# Motherboard.net
KiCad netlist of a schematic drawn in Altium Designer
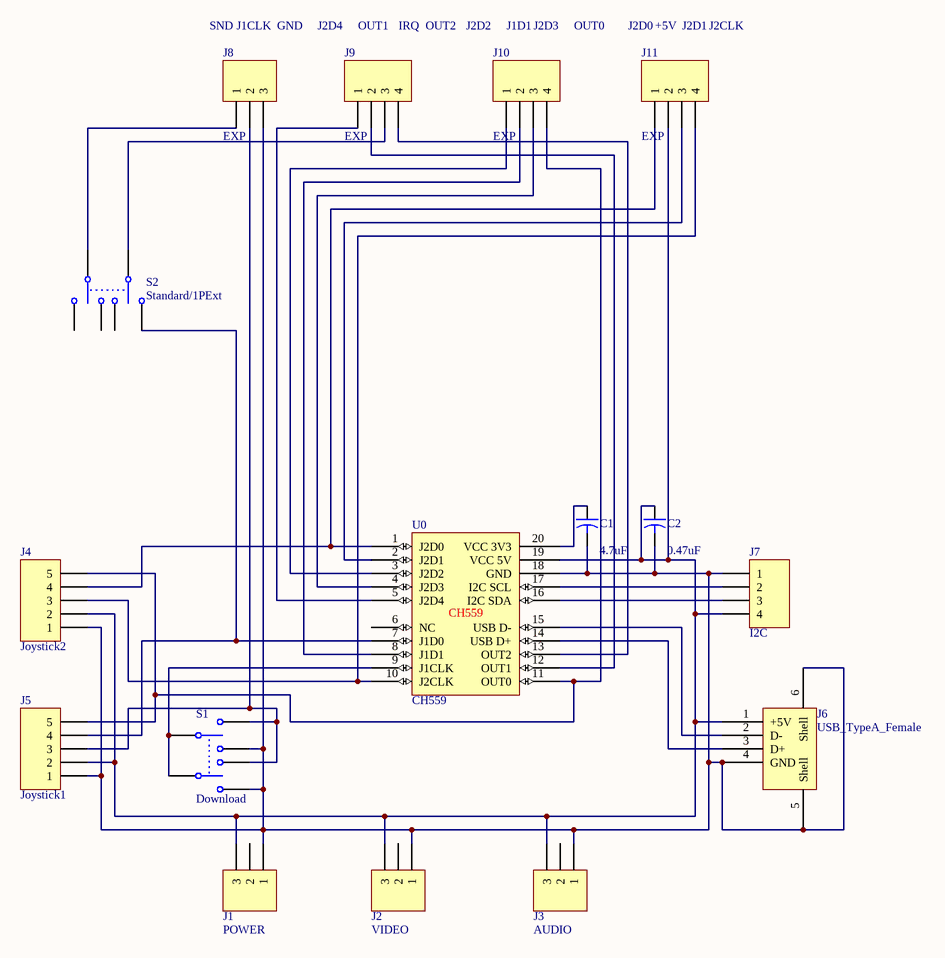
[diagram p0: Motherboard.SchDoc]

(export (version "E")
  (design (tool "Eeschema 10.0.6"))
  (components
    (comp (ref "C1")
      (value "4.7uF")
      (footprint "CAPR5-4X5")
      (description "Capacitor")
      (fields (field (name "Comment") "Cap2") (field (name "PUBLISHER") "Altium Limited"))
      (libsource (lib "Miscellaneous Devices") (part "Cap2"))
    )
    (comp (ref "C2")
      (value "0.47uF")
      (footprint "CAPR5-4X5")
      (description "Capacitor")
      (fields (field (name "Comment") "Cap2") (field (name "PUBLISHER") "Altium Limited"))
      (libsource (lib "Miscellaneous Devices") (part "Cap2"))
    )
    (comp (ref "J1")
      (value "POWER")
      (footprint "HDR1X3H")
      (description "Header, 3-Pin, Right Angle")
      (fields (field (name "PUBLISHER") "Altium Limited"))
      (libsource (lib "Miscellaneous Connectors") (part "Header 3H"))
    )
    (comp (ref "J2")
      (value "VIDEO")
      (footprint "HDR1X3H")
      (description "Header, 3-Pin, Right Angle")
      (fields (field (name "PUBLISHER") "Altium Limited"))
      (libsource (lib "Miscellaneous Connectors") (part "Header 3H"))
    )
    (comp (ref "J3")
      (value "AUDIO")
      (footprint "HDR1X3H")
      (description "Header, 3-Pin, Right Angle")
      (fields (field (name "PUBLISHER") "Altium Limited"))
      (libsource (lib "Miscellaneous Connectors") (part "Header 3H"))
    )
    (comp (ref "J4")
      (value "Joystick2")
      (footprint "HDR1X5H")
      (description "Header, 5-Pin, Right Angle")
      (fields (field (name "PUBLISHER") "Altium Limited"))
      (libsource (lib "Miscellaneous Connectors") (part "Header 5H"))
    )
    (comp (ref "J5")
      (value "Joystick1")
      (footprint "HDR1X5H")
      (description "Header, 5-Pin, Right Angle")
      (fields (field (name "PUBLISHER") "Altium Limited"))
      (libsource (lib "Miscellaneous Connectors") (part "Header 5H"))
    )
    (comp (ref "J6")
      (value "USB_TypeA_Female")
      (footprint "USB_TypeA_Female")
      (libsource (lib "USB_TypeA_Female") (part "USB_TypeA_Female"))
    )
    (comp (ref "J7")
      (value "I2C")
      (footprint "HDR1X4H")
      (description "Header, 4-Pin, Right Angle")
      (fields (field (name "PUBLISHER") "Altium Limited"))
      (libsource (lib "") (part "Header 4H_1"))
    )
    (comp (ref "J8")
      (value "EXP")
      (footprint "HDR1X3H")
      (description "Header, 3-Pin, Right Angle")
      (fields (field (name "PUBLISHER") "Altium Limited"))
      (libsource (lib "") (part "Header 3H_1"))
    )
    (comp (ref "J9")
      (value "EXP")
      (footprint "HDR1X4H")
      (description "Header, 4-Pin, Right Angle")
      (fields (field (name "PUBLISHER") "Altium Limited"))
      (libsource (lib "Miscellaneous Connectors") (part "Header 4H"))
    )
    (comp (ref "J10")
      (value "EXP")
      (footprint "HDR1X4H")
      (description "Header, 4-Pin, Right Angle")
      (fields (field (name "PUBLISHER") "Altium Limited"))
      (libsource (lib "Miscellaneous Connectors") (part "Header 4H"))
    )
    (comp (ref "J11")
      (value "EXP")
      (footprint "HDR1X4H")
      (description "Header, 4-Pin, Right Angle")
      (fields (field (name "PUBLISHER") "Altium Limited"))
      (libsource (lib "Miscellaneous Connectors") (part "Header 4H"))
    )
    (comp (ref "S1")
      (value "Download")
      (footprint "DPDT-6")
      (description "Double-Pole, Double-Throw Switch")
      (fields (field (name "PUBLISHER") "Altium Limited"))
      (libsource (lib "Miscellaneous Devices") (part "SW-DPDT"))
    )
    (comp (ref "S2")
      (value "Standard/1PExt")
      (footprint "DPDT-6")
      (description "Double-Pole, Double-Throw Switch")
      (fields (field (name "PUBLISHER") "Altium Limited"))
      (libsource (lib "Miscellaneous Devices") (part "SW-DPDT"))
    )
    (comp (ref "U0") (value "CH559") (footprint "SSOP20") (libsource (lib "CH559") (part "CH559")))
  )
  (nets
    (net (code "1") (name "Net-(J5-Pad3)") (class "Default")
      (node (ref "J5") (pin "3") (pinfunction "3_3") (pintype "passive"))
      (node (ref "J8") (pin "2") (pinfunction "2_2") (pintype "passive"))
      (node (ref "S1") (pin "2") (pinfunction "2_2") (pintype "passive"))
      (node (ref "S1") (pin "5") (pinfunction "5_5") (pintype "passive"))
    )
    (net (code "2") (name "Net-(J6-+5V)") (class "Default")
      (node (ref "C2") (pin "1") (pinfunction "1_1") (pintype "passive"))
      (node (ref "J1") (pin "3") (pinfunction "3_3") (pintype "passive"))
      (node (ref "J11") (pin "2") (pinfunction "2_2") (pintype "passive"))
      (node (ref "J2") (pin "3") (pinfunction "3_3") (pintype "passive"))
      (node (ref "J3") (pin "3") (pinfunction "3_3") (pintype "passive"))
      (node (ref "J4") (pin "2") (pinfunction "2_2") (pintype "passive"))
      (node (ref "J5") (pin "2") (pinfunction "2_2") (pintype "passive"))
      (node (ref "J6") (pin "1") (pinfunction "+5V_1") (pintype "passive"))
      (node (ref "J7") (pin "4") (pinfunction "4_4") (pintype "passive"))
      (node (ref "U0") (pin "19") (pinfunction "VCC_5V_19") (pintype "power_in"))
    )
    (net (code "3") (name "Net-(J6-D+)") (class "Default")
      (node (ref "J6") (pin "3") (pinfunction "D+_3") (pintype "passive"))
      (node (ref "U0") (pin "14") (pinfunction "USB_D+_14") (pintype "bidirectional"))
    )
    (net (code "4") (name "Net-(J6-D-)") (class "Default")
      (node (ref "J6") (pin "2") (pinfunction "D-_2") (pintype "passive"))
      (node (ref "U0") (pin "15") (pinfunction "USB_D-_15") (pintype "bidirectional"))
    )
    (net (code "5") (name "Net-(J6-GND)") (class "Default")
      (node (ref "C1") (pin "2") (pinfunction "2_2") (pintype "passive"))
      (node (ref "C2") (pin "2") (pinfunction "2_2") (pintype "passive"))
      (node (ref "J1") (pin "1") (pinfunction "1_1") (pintype "passive"))
      (node (ref "J2") (pin "1") (pinfunction "1_1") (pintype "passive"))
      (node (ref "J3") (pin "1") (pinfunction "1_1") (pintype "passive"))
      (node (ref "J4") (pin "1") (pinfunction "1_1") (pintype "passive"))
      (node (ref "J5") (pin "1") (pinfunction "1_1") (pintype "passive"))
      (node (ref "J6") (pin "4") (pinfunction "GND_4") (pintype "passive"))
      (node (ref "J6") (pin "5") (pinfunction "Shell_5") (pintype "passive"))
      (node (ref "J6") (pin "6") (pinfunction "Shell_6") (pintype "passive"))
      (node (ref "J7") (pin "1") (pinfunction "1_1") (pintype "passive"))
      (node (ref "J8") (pin "3") (pinfunction "3_3") (pintype "passive"))
      (node (ref "S1") (pin "3") (pinfunction "3_3") (pintype "passive"))
      (node (ref "S1") (pin "6") (pinfunction "6_6") (pintype "passive"))
      (node (ref "U0") (pin "18") (pinfunction "GND_18") (pintype "power_in"))
    )
    (net (code "6") (name "Net-(J8-Pad1)") (class "Default")
      (node (ref "J8") (pin "1") (pinfunction "1_1") (pintype "passive"))
      (node (ref "S2") (pin "4") (pinfunction "4_4") (pintype "passive"))
    )
    (net (code "7") (name "Net-(J9-Pad3)") (class "Default")
      (node (ref "J9") (pin "3") (pinfunction "3_3") (pintype "passive"))
      (node (ref "S2") (pin "1") (pinfunction "1_1") (pintype "passive"))
    )
    (net (code "8") (name "Net-(U0-I2C_SCL)") (class "Default")
      (node (ref "J7") (pin "2") (pinfunction "2_2") (pintype "passive"))
      (node (ref "U0") (pin "17") (pinfunction "I2C_SCL_17") (pintype "bidirectional"))
    )
    (net (code "9") (name "Net-(U0-I2C_SDA)") (class "Default")
      (node (ref "J7") (pin "3") (pinfunction "3_3") (pintype "passive"))
      (node (ref "U0") (pin "16") (pinfunction "I2C_SDA_16") (pintype "bidirectional"))
    )
    (net (code "10") (name "Net-(U0-J1CLK)") (class "Default")
      (node (ref "S1") (pin "1") (pinfunction "1_1") (pintype "passive"))
      (node (ref "S1") (pin "4") (pinfunction "4_4") (pintype "passive"))
      (node (ref "U0") (pin "9") (pinfunction "J1CLK_9") (pintype "bidirectional"))
    )
    (net (code "11") (name "Net-(U0-J1D0)") (class "Default")
      (node (ref "J5") (pin "4") (pinfunction "4_4") (pintype "passive"))
      (node (ref "S2") (pin "2") (pinfunction "2_2") (pintype "passive"))
      (node (ref "U0") (pin "7") (pinfunction "J1D0_7") (pintype "bidirectional"))
    )
    (net (code "12") (name "Net-(U0-J1D1)") (class "Default")
      (node (ref "J10") (pin "2") (pinfunction "2_2") (pintype "passive"))
      (node (ref "U0") (pin "8") (pinfunction "J1D1_8") (pintype "bidirectional"))
    )
    (net (code "13") (name "Net-(U0-J2CLK)") (class "Default")
      (node (ref "J11") (pin "4") (pinfunction "4_4") (pintype "passive"))
      (node (ref "J4") (pin "3") (pinfunction "3_3") (pintype "passive"))
      (node (ref "U0") (pin "10") (pinfunction "J2CLK_10") (pintype "bidirectional"))
    )
    (net (code "14") (name "Net-(U0-J2D0)") (class "Default")
      (node (ref "J11") (pin "1") (pinfunction "1_1") (pintype "passive"))
      (node (ref "J4") (pin "4") (pinfunction "4_4") (pintype "passive"))
      (node (ref "U0") (pin "1") (pinfunction "J2D0_1") (pintype "bidirectional"))
    )
    (net (code "15") (name "Net-(U0-J2D1)") (class "Default")
      (node (ref "J11") (pin "3") (pinfunction "3_3") (pintype "passive"))
      (node (ref "U0") (pin "2") (pinfunction "J2D1_2") (pintype "bidirectional"))
    )
    (net (code "16") (name "Net-(U0-J2D2)") (class "Default")
      (node (ref "J10") (pin "1") (pinfunction "1_1") (pintype "passive"))
      (node (ref "U0") (pin "3") (pinfunction "J2D2_3") (pintype "bidirectional"))
    )
    (net (code "17") (name "Net-(U0-J2D3)") (class "Default")
      (node (ref "J10") (pin "3") (pinfunction "3_3") (pintype "passive"))
      (node (ref "U0") (pin "4") (pinfunction "J2D3_4") (pintype "bidirectional"))
    )
    (net (code "18") (name "Net-(U0-J2D4)") (class "Default")
      (node (ref "J9") (pin "1") (pinfunction "1_1") (pintype "passive"))
      (node (ref "U0") (pin "5") (pinfunction "J2D4_5") (pintype "bidirectional"))
    )
    (net (code "19") (name "Net-(U0-OUT0)") (class "Default")
      (node (ref "J10") (pin "4") (pinfunction "4_4") (pintype "passive"))
      (node (ref "J4") (pin "5") (pinfunction "5_5") (pintype "passive"))
      (node (ref "J5") (pin "5") (pinfunction "5_5") (pintype "passive"))
      (node (ref "U0") (pin "11") (pinfunction "OUT0_11") (pintype "bidirectional"))
    )
    (net (code "20") (name "Net-(U0-OUT1)") (class "Default")
      (node (ref "J9") (pin "2") (pinfunction "2_2") (pintype "passive"))
      (node (ref "U0") (pin "12") (pinfunction "OUT1_12") (pintype "bidirectional"))
    )
    (net (code "21") (name "Net-(U0-OUT2)") (class "Default")
      (node (ref "J9") (pin "4") (pinfunction "4_4") (pintype "passive"))
      (node (ref "U0") (pin "13") (pinfunction "OUT2_13") (pintype "bidirectional"))
    )
    (net (code "22") (name "Net-(U0-VCC_3V3)") (class "Default")
      (node (ref "C1") (pin "1") (pinfunction "1_1") (pintype "passive"))
      (node (ref "U0") (pin "20") (pinfunction "VCC_3V3_20") (pintype "power_in"))
    )
    (net (code "23") (name "unconnected-(J1-Pad2)") (class "Default")
      (node (ref "J1") (pin "2") (pinfunction "2_2") (pintype "passive"))
    )
    (net (code "24") (name "unconnected-(J2-Pad2)") (class "Default")
      (node (ref "J2") (pin "2") (pinfunction "2_2") (pintype "passive"))
    )
    (net (code "25") (name "unconnected-(J3-Pad2)") (class "Default")
      (node (ref "J3") (pin "2") (pinfunction "2_2") (pintype "passive"))
    )
    (net (code "26") (name "unconnected-(S2-Pad3)") (class "Default")
      (node (ref "S2") (pin "3") (pinfunction "3_3") (pintype "passive"))
    )
    (net (code "27") (name "unconnected-(S2-Pad5)") (class "Default")
      (node (ref "S2") (pin "5") (pinfunction "5_5") (pintype "passive"))
    )
    (net (code "28") (name "unconnected-(S2-Pad6)") (class "Default")
      (node (ref "S2") (pin "6") (pinfunction "6_6") (pintype "passive"))
    )
    (net (code "29") (name "unconnected-(U0-NC-Pad6)") (class "Default")
      (node (ref "U0") (pin "6") (pinfunction "NC_6") (pintype "bidirectional"))
    )
  )
)
